# 03_PowerSupply.net
KiCad netlist of a schematic drawn in Altium Designer
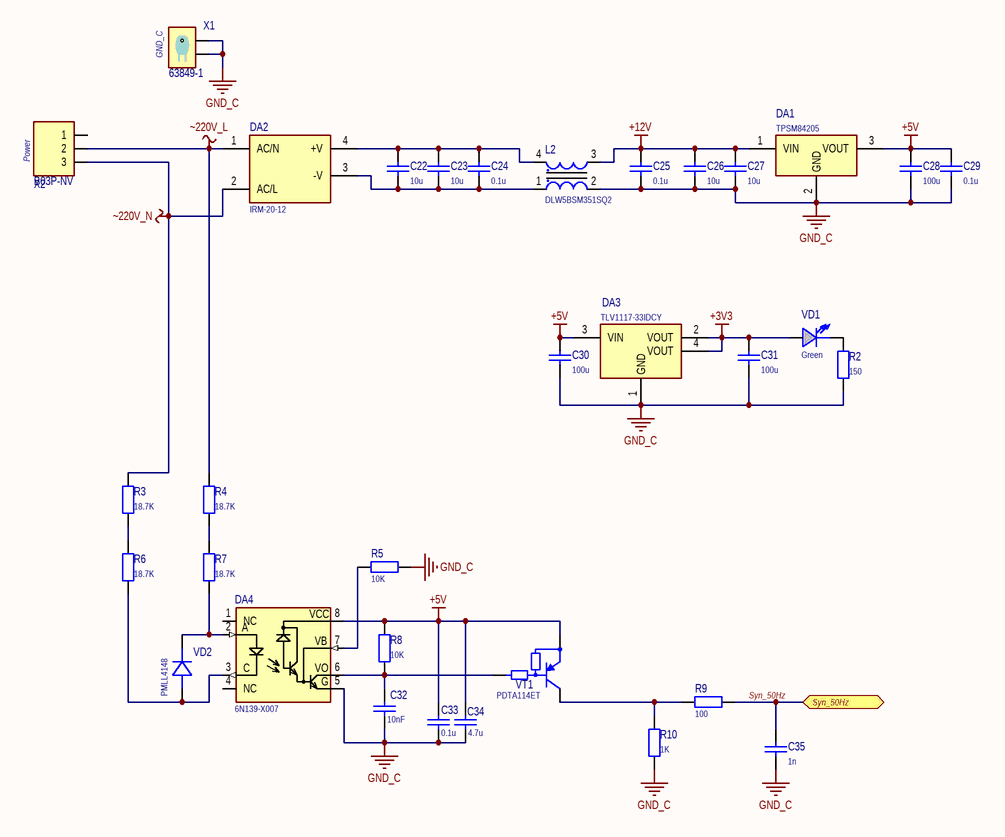
[diagram p0: 03_PowerSupply.SchDoc]

(export (version "E")
  (design (tool "Eeschema 10.0.6"))
  (components
    (comp (ref "C22")
      (value "10u")
      (footprint "mainLib:SMD_C_1206")
      (description "SMD C 1206 MURATA 25V 20% X5R")
      (fields (field (name "PARTNUMBER") "GRM31MR61E106M") (field (name "MANUFACTURER") "MURATA"))
      (libsource (lib "mainRCLib") (part "C1206 10u 25V 20%"))
    )
    (comp (ref "C23")
      (value "10u")
      (footprint "mainLib:SMD_C_1206")
      (description "SMD C 1206 MURATA 25V 20% X5R")
      (fields (field (name "PARTNUMBER") "GRM31MR61E106M") (field (name "MANUFACTURER") "MURATA"))
      (libsource (lib "mainRCLib") (part "C1206 10u 25V 20%"))
    )
    (comp (ref "C24")
      (value "0.1u")
      (footprint "mainLib:SMD_C_0603")
      (description "SMD C 0603 MURATA 50V 10% X7R")
      (fields (field (name "PARTNUMBER") "GRM188R71H104K") (field (name "MANUFACTURER") "MURATA"))
      (libsource (lib "mainRCLib") (part "C0603 0.1u 50V 10%"))
    )
    (comp (ref "C25")
      (value "0.1u")
      (footprint "mainLib:SMD_C_0603")
      (description "SMD C 0603 MURATA 50V 10% X7R")
      (fields (field (name "PARTNUMBER") "GRM188R71H104K") (field (name "MANUFACTURER") "MURATA"))
      (libsource (lib "mainRCLib") (part "C0603 0.1u 50V 10%"))
    )
    (comp (ref "C26")
      (value "10u")
      (footprint "mainLib:SMD_C_1206")
      (description "SMD C 1206 MURATA 25V 20% X5R")
      (fields (field (name "PARTNUMBER") "GRM31MR61E106M") (field (name "MANUFACTURER") "MURATA"))
      (libsource (lib "mainRCLib") (part "C1206 10u 25V 20%"))
    )
    (comp (ref "C27")
      (value "10u")
      (footprint "mainLib:SMD_C_1206")
      (description "SMD C 1206 MURATA 25V 20% X5R")
      (fields (field (name "PARTNUMBER") "GRM31MR61E106M") (field (name "MANUFACTURER") "MURATA"))
      (libsource (lib "mainRCLib") (part "C1206 10u 25V 20%"))
    )
    (comp (ref "C28")
      (value "100u")
      (footprint "mainLib:SMD_C_0805")
      (description "SMD 0805 MURATA 6.3V 20% X5R")
      (fields (field (name "PARTNUMBER") "GRM21BR60J107M") (field (name "MANUFACTURER") "MURATA"))
      (libsource (lib "mainRCLib") (part "C0805 100u 6.3V 20% X5R"))
    )
    (comp (ref "C29")
      (value "0.1u")
      (footprint "mainLib:SMD_C_0603")
      (description "SMD C 0603 MURATA 50V 10% X7R")
      (fields (field (name "PARTNUMBER") "GRM188R71H104K") (field (name "MANUFACTURER") "MURATA"))
      (libsource (lib "mainRCLib") (part "C0603 0.1u 50V 10%"))
    )
    (comp (ref "C30")
      (value "100u")
      (footprint "mainLib:SMD_C_0805")
      (description "SMD 0805 MURATA 6.3V 20% X5R")
      (fields (field (name "PARTNUMBER") "GRM21BR60J107M") (field (name "MANUFACTURER") "MURATA"))
      (libsource (lib "mainRCLib") (part "C0805 100u 6.3V 20% X5R"))
    )
    (comp (ref "C31")
      (value "100u")
      (footprint "mainLib:SMD_C_0805")
      (description "SMD 0805 MURATA 6.3V 20% X5R")
      (fields (field (name "PARTNUMBER") "GRM21BR60J107M") (field (name "MANUFACTURER") "MURATA"))
      (libsource (lib "mainRCLib") (part "C0805 100u 6.3V 20% X5R"))
    )
    (comp (ref "C32")
      (value "10nF")
      (footprint "mainLib:SMD_C_0603")
      (description "SMD C 0603 MURATA 100V 10% X7R")
      (fields (field (name "PARTNUMBER") "GRJ188R72A103KE11#") (field (name "MANUFACTURER") "MURATA"))
      (libsource (lib "mainRCLib") (part "C0603 10nF 100V 10%"))
    )
    (comp (ref "C33")
      (value "0.1u")
      (footprint "mainLib:SMD_C_0603")
      (description "SMD C 0603 MURATA 50V 10% X7R")
      (fields (field (name "PARTNUMBER") "GRM188R71H104K") (field (name "MANUFACTURER") "MURATA"))
      (libsource (lib "mainRCLib") (part "C0603 0.1u 50V 10%"))
    )
    (comp (ref "C34")
      (value "4.7u")
      (footprint "mainLib:SMD_C_0805")
      (description "SMD C 0805 MURATA 50V 5% NP0")
      (fields (field (name "PARTNUMBER") "GRM21BR61E475M") (field (name "MANUFACTURER") "MURATA"))
      (libsource (lib "mainRCLib") (part "C0805 4.7u 25V 20%  X5R"))
    )
    (comp (ref "C35")
      (value "1n")
      (footprint "mainLib:SMD_C_0603")
      (description "SMD C 0603 MURATA 50V 5% NP0")
      (fields (field (name "PARTNUMBER") "GRM1885C1H102JA01") (field (name "MANUFACTURER") "MURATA"))
      (libsource (lib "mainRCLib") (part "C0603 1n 50V 5%"))
    )
    (comp (ref "DA1")
      (value "TPSM84205")
      (footprint "mainLib:EAB (SIP DCDC Module)")
      (description "1.5A 5Vout up to 28 Vin StepDown module")
      (fields (field (name "MANUFACTURER") "Texas Instrument"))
      (libsource (lib "mainLib") (part "TPSM84205"))
    )
    (comp (ref "DA2")
      (value "IRM-20-12")
      (footprint "mainLib:IRM-20-12")
      (description "20W 12VDC 1.85A PCB")
      (fields (field (name "MANUFACTURER") "Mean Well"))
      (libsource (lib "mainLib") (part "IRM-20-12"))
    )
    (comp (ref "DA3")
      (value "TLV1117-33IDCY")
      (footprint "mainLib:SOT-223_M")
      (description "Voltage regulator 3.3V 800mA")
      (fields (field (name "MANUFACTURER") "Texas Instrument"))
      (libsource (lib "mainLib") (part "TLV1117-33IDCY"))
    )
    (comp (ref "DA4")
      (value "6N139-X007")
      (footprint "mainLib:6N139-X007")
      (description "Optocoupler darlingron 5.3kV 100 kbit/s")
      (fields (field (name "MANUFACTURER") "Vishay"))
      (libsource (lib "mainLib") (part "6N139-X007"))
    )
    (comp (ref "L2")
      (value "DLW5BSM351SQ2")
      (footprint "mainLib:DLW5BS(AH)")
      (description "SMD Common Mode Choke Coil 2A Z = 350 Ohm / 100 MHz")
      (fields (field (name "MANUFACTURER") "MURATA"))
      (libsource (lib "mainLib") (part "DLW5BSM351SQ2"))
    )
    (comp (ref "R2")
      (value "150")
      (footprint "mainLib:SMD_R_0805")
      (description "SMD 0805 VISHAY 0.125W 150V 1% 100ppm")
      (fields (field (name "PARTNUMBER") "CRCW0805150RFK") (field (name "MANUFACTURER") "VISHAY"))
      (libsource (lib "mainRCLib") (part "R0805 150 1%"))
    )
    (comp (ref "R3")
      (value "18.7K")
      (footprint "mainLib:SMD_R_1206")
      (description "SMD R 1206 VISHAY 0.25W 200V 1% 100ppm")
      (fields (field (name "PARTNUMBER") "CRCW120618K7FK") (field (name "MANUFACTURER") "VISHAY"))
      (libsource (lib "mainRCLib") (part "R1206 18.7K 1%"))
    )
    (comp (ref "R4")
      (value "18.7K")
      (footprint "mainLib:SMD_R_1206")
      (description "SMD R 1206 VISHAY 0.25W 200V 1% 100ppm")
      (fields (field (name "PARTNUMBER") "CRCW120618K7FK") (field (name "MANUFACTURER") "VISHAY"))
      (libsource (lib "mainRCLib") (part "R1206 18.7K 1%"))
    )
    (comp (ref "R5")
      (value "10K")
      (footprint "SMD_R_0603")
      (description "SMD R 0603 VISHAY 0.1W 75V 1% 100ppm")
      (fields (field (name "PARTNUMBER") "CRCW060310K0FK") (field (name "MANUFACTURER") "VISHAY"))
      (libsource (lib "mainRCLib") (part "R0603 10К 1%"))
    )
    (comp (ref "R6")
      (value "18.7K")
      (footprint "mainLib:SMD_R_1206")
      (description "SMD R 1206 VISHAY 0.25W 200V 1% 100ppm")
      (fields (field (name "PARTNUMBER") "CRCW120618K7FK") (field (name "MANUFACTURER") "VISHAY"))
      (libsource (lib "mainRCLib") (part "R1206 18.7K 1%"))
    )
    (comp (ref "R7")
      (value "18.7K")
      (footprint "mainLib:SMD_R_1206")
      (description "SMD R 1206 VISHAY 0.25W 200V 1% 100ppm")
      (fields (field (name "PARTNUMBER") "CRCW120618K7FK") (field (name "MANUFACTURER") "VISHAY"))
      (libsource (lib "mainRCLib") (part "R1206 18.7K 1%"))
    )
    (comp (ref "R8")
      (value "10K")
      (footprint "mainLib:SMD_R_0805")
      (description "SMD R 0805 VISHAY 0.125W 150V 1% 100ppm")
      (fields (field (name "PARTNUMBER") "CRCW080510K0FK") (field (name "MANUFACTURER") "VISHAY"))
      (libsource (lib "mainRCLib") (part "R0805 10K 1%"))
    )
    (comp (ref "R9")
      (value "100")
      (footprint "SMD_R_0603")
      (description "SMD R 0603 VISHAY 0.1W 75V 1% 100ppm")
      (fields (field (name "PARTNUMBER") "CRCW0603100RFK") (field (name "MANUFACTURER") "VISHAY"))
      (libsource (lib "mainRCLib") (part "R0603 100 1%"))
    )
    (comp (ref "R10")
      (value "1K")
      (footprint "mainLib:SMD_R_0603")
      (description "SMD R 0603 VISHAY 0.1W 75V 1% 100ppm")
      (fields (field (name "PARTNUMBER") "CRCW06031K00FK") (field (name "MANUFACTURER") "VISHAY"))
      (libsource (lib "mainRCLib") (part "R0603 1K 1%"))
    )
    (comp (ref "VD1")
      (value "Green")
      (footprint "mainLib:SMD_LED_LL_Green")
      (description "LED Green SMD")
      (fields (field (name "PARTNUMBER") "LL-S172GC-2A") (field (name "MANUFACTURER") "Lucky Light"))
      (libsource (lib "mainLib") (part "LL-S172GC-2A"))
    )
    (comp (ref "VD2")
      (value "PMLL4148")
      (footprint "mainLib:SOD80C")
      (description "If=0.2A, Vf=1V Vrrm=100V Diode (SOD80C)")
      (fields (field (name "MANUFACTURER") "NXP Semiconductors"))
      (libsource (lib "mainLib") (part "PMLL4148"))
    )
    (comp (ref "VT1")
      (value "PDTA114ET")
      (footprint "mainLib:SOT23-3")
      (description "Digital Transistor (BRT), R1=10 kOhm, R2=10 kOhm, PNP Transistor")
      (fields (field (name "MANUFACTURER") "NXP"))
      (libsource (lib "mainLib") (part "PDTA114ET"))
    )
    (comp (ref "X1")
      (value "63849-1")
      (footprint "mainLib:63849-1")
      (description "PCB, 6.3х0.8, hole")
      (fields (field (name "MANUFACTURER") "TE Connectivity"))
      (libsource (lib "mainLib") (part "63849-1"))
    )
    (comp (ref "X2")
      (value "B03P-NV")
      (footprint "mainLib:B03P-NV (power)")
      (description "NV 3 конт LS=5.0 10A 250V PCB")
      (fields (field (name "MANUFACTURER") "JST"))
      (libsource (lib "mainLib") (part "B03P-NV"))
    )
  )
  (nets
    (net (code "1") (name "+3V3") (class "Default")
      (node (ref "C31") (pin "1") (pinfunction "1_1") (pintype "passive"))
      (node (ref "DA3") (pin "2") (pinfunction "VOUT_2") (pintype "power_in"))
      (node (ref "DA3") (pin "4") (pinfunction "VOUT_4") (pintype "power_in"))
      (node (ref "VD1") (pin "1") (pinfunction "ANODE_1") (pintype "passive"))
    )
    (net (code "2") (name "+5V") (class "Default")
      (node (ref "C28") (pin "1") (pinfunction "1_1") (pintype "passive"))
      (node (ref "C29") (pin "2") (pinfunction "2_2") (pintype "passive"))
      (node (ref "C30") (pin "1") (pinfunction "1_1") (pintype "passive"))
      (node (ref "C33") (pin "2") (pinfunction "2_2") (pintype "passive"))
      (node (ref "C34") (pin "2") (pinfunction "2_2") (pintype "passive"))
      (node (ref "DA1") (pin "3") (pinfunction "VOUT_3") (pintype "power_in"))
      (node (ref "DA3") (pin "3") (pinfunction "VIN_3") (pintype "power_in"))
      (node (ref "DA4") (pin "8") (pinfunction "VCC_8") (pintype "power_in"))
      (node (ref "R8") (pin "2") (pinfunction "2_2") (pintype "passive"))
      (node (ref "VT1") (pin "2") (pinfunction "E_2") (pintype "passive"))
    )
    (net (code "3") (name "+12V") (class "Default")
      (node (ref "C25") (pin "2") (pinfunction "2_2") (pintype "passive"))
      (node (ref "C26") (pin "2") (pinfunction "2_2") (pintype "passive"))
      (node (ref "C27") (pin "2") (pinfunction "2_2") (pintype "passive"))
      (node (ref "DA1") (pin "1") (pinfunction "VIN_1") (pintype "power_in"))
      (node (ref "L2") (pin "3") (pinfunction "3_3") (pintype "passive"))
    )
    (net (code "4") (name "/Syn_50Hz") (class "Default")
      (node (ref "C35") (pin "2") (pinfunction "2_2") (pintype "passive"))
      (node (ref "R9") (pin "2") (pinfunction "2_2") (pintype "passive"))
    )
    (net (code "5") (name "GND_C") (class "Default")
      (node (ref "C25") (pin "1") (pinfunction "1_1") (pintype "passive"))
      (node (ref "C26") (pin "1") (pinfunction "1_1") (pintype "passive"))
      (node (ref "C27") (pin "1") (pinfunction "1_1") (pintype "passive"))
      (node (ref "C28") (pin "2") (pinfunction "2_2") (pintype "passive"))
      (node (ref "C29") (pin "1") (pinfunction "1_1") (pintype "passive"))
      (node (ref "C30") (pin "2") (pinfunction "2_2") (pintype "passive"))
      (node (ref "C31") (pin "2") (pinfunction "2_2") (pintype "passive"))
      (node (ref "C32") (pin "1") (pinfunction "1_1") (pintype "passive"))
      (node (ref "C33") (pin "1") (pinfunction "1_1") (pintype "passive"))
      (node (ref "C34") (pin "1") (pinfunction "1_1") (pintype "passive"))
      (node (ref "C35") (pin "1") (pinfunction "1_1") (pintype "passive"))
      (node (ref "DA1") (pin "2") (pinfunction "GND_2") (pintype "power_in"))
      (node (ref "DA3") (pin "1") (pinfunction "GND_1") (pintype "power_in"))
      (node (ref "DA4") (pin "5") (pinfunction "5_5") (pintype "power_in"))
      (node (ref "L2") (pin "2") (pinfunction "2_2") (pintype "passive"))
      (node (ref "R10") (pin "1") (pinfunction "1_1") (pintype "passive"))
      (node (ref "R2") (pin "1") (pinfunction "1_1") (pintype "passive"))
      (node (ref "R5") (pin "2") (pinfunction "2_2") (pintype "passive"))
      (node (ref "X1") (pin "1") (pinfunction "1_1") (pintype "passive"))
      (node (ref "X1") (pin "2") (pinfunction "2_2") (pintype "passive"))
    )
    (net (code "6") (name "Net-(DA2-+V)") (class "Default")
      (node (ref "C22") (pin "2") (pinfunction "2_2") (pintype "passive"))
      (node (ref "C23") (pin "2") (pinfunction "2_2") (pintype "passive"))
      (node (ref "C24") (pin "2") (pinfunction "2_2") (pintype "passive"))
      (node (ref "DA2") (pin "4") (pinfunction "+V_4") (pintype "passive"))
      (node (ref "L2") (pin "4") (pinfunction "4_4") (pintype "passive"))
    )
    (net (code "7") (name "Net-(DA2--V)") (class "Default")
      (node (ref "C22") (pin "1") (pinfunction "1_1") (pintype "passive"))
      (node (ref "C23") (pin "1") (pinfunction "1_1") (pintype "passive"))
      (node (ref "C24") (pin "1") (pinfunction "1_1") (pintype "passive"))
      (node (ref "DA2") (pin "3") (pinfunction "-V_3") (pintype "passive"))
      (node (ref "L2") (pin "1") (pinfunction "1_1") (pintype "passive"))
    )
    (net (code "8") (name "Net-(DA4-C)") (class "Default")
      (node (ref "DA4") (pin "3") (pinfunction "C_3") (pintype "output"))
      (node (ref "R6") (pin "1") (pinfunction "1_1") (pintype "passive"))
      (node (ref "VD2") (pin "1") (pinfunction "ANODE_1") (pintype "passive"))
    )
    (net (code "9") (name "Net-(DA4-VB)") (class "Default")
      (node (ref "DA4") (pin "7") (pinfunction "VB_7") (pintype "input"))
      (node (ref "R5") (pin "1") (pinfunction "1_1") (pintype "passive"))
    )
    (net (code "10") (name "Net-(R3-Pad1)") (class "Default")
      (node (ref "R3") (pin "1") (pinfunction "1_1") (pintype "passive"))
      (node (ref "R6") (pin "2") (pinfunction "2_2") (pintype "passive"))
    )
    (net (code "11") (name "Net-(R4-Pad1)") (class "Default")
      (node (ref "R4") (pin "1") (pinfunction "1_1") (pintype "passive"))
      (node (ref "R7") (pin "2") (pinfunction "2_2") (pintype "passive"))
    )
    (net (code "12") (name "Net-(VD1-CATHODE)") (class "Default")
      (node (ref "R2") (pin "2") (pinfunction "2_2") (pintype "passive"))
      (node (ref "VD1") (pin "2") (pinfunction "CATHODE_2") (pintype "passive"))
    )
    (net (code "13") (name "Net-(VD2-CATHODE)") (class "Default")
      (node (ref "DA4") (pin "2") (pinfunction "2_2") (pintype "input"))
      (node (ref "R7") (pin "1") (pinfunction "1_1") (pintype "passive"))
      (node (ref "VD2") (pin "2") (pinfunction "CATHODE_2") (pintype "passive"))
    )
    (net (code "14") (name "Net-(VT1-B)") (class "Default")
      (node (ref "C32") (pin "2") (pinfunction "2_2") (pintype "passive"))
      (node (ref "DA4") (pin "6") (pinfunction "6_6") (pintype "open_collector"))
      (node (ref "R8") (pin "1") (pinfunction "1_1") (pintype "passive"))
      (node (ref "VT1") (pin "1") (pinfunction "B_1") (pintype "passive"))
    )
    (net (code "15") (name "Net-(VT1-C)") (class "Default")
      (node (ref "R10") (pin "2") (pinfunction "2_2") (pintype "passive"))
      (node (ref "R9") (pin "1") (pinfunction "1_1") (pintype "passive"))
      (node (ref "VT1") (pin "3") (pinfunction "C_3") (pintype "passive"))
    )
    (net (code "16") (name "unconnected-(DA4-NC-Pad1)") (class "Default")
      (node (ref "DA4") (pin "1") (pinfunction "NC_1") (pintype "passive"))
    )
    (net (code "17") (name "unconnected-(DA4-NC-Pad4)") (class "Default")
      (node (ref "DA4") (pin "4") (pinfunction "NC_4") (pintype "passive"))
    )
    (net (code "18") (name "unconnected-(X2-Pad1)") (class "Default")
      (node (ref "X2") (pin "1") (pinfunction "1_1") (pintype "passive"))
    )
    (net (code "19") (name "~220V_L") (class "Default")
      (node (ref "DA2") (pin "1") (pinfunction "AC/N_1") (pintype "passive"))
      (node (ref "R4") (pin "2") (pinfunction "2_2") (pintype "passive"))
      (node (ref "X2") (pin "2") (pinfunction "2_2") (pintype "passive"))
    )
    (net (code "20") (name "~220V_N") (class "Default")
      (node (ref "DA2") (pin "2") (pinfunction "AC/L_2") (pintype "passive"))
      (node (ref "R3") (pin "2") (pinfunction "2_2") (pintype "passive"))
      (node (ref "X2") (pin "3") (pinfunction "3_3") (pintype "passive"))
    )
  )
)
